# USB_to_UART.net
KiCad netlist of a schematic drawn in Altium Designer
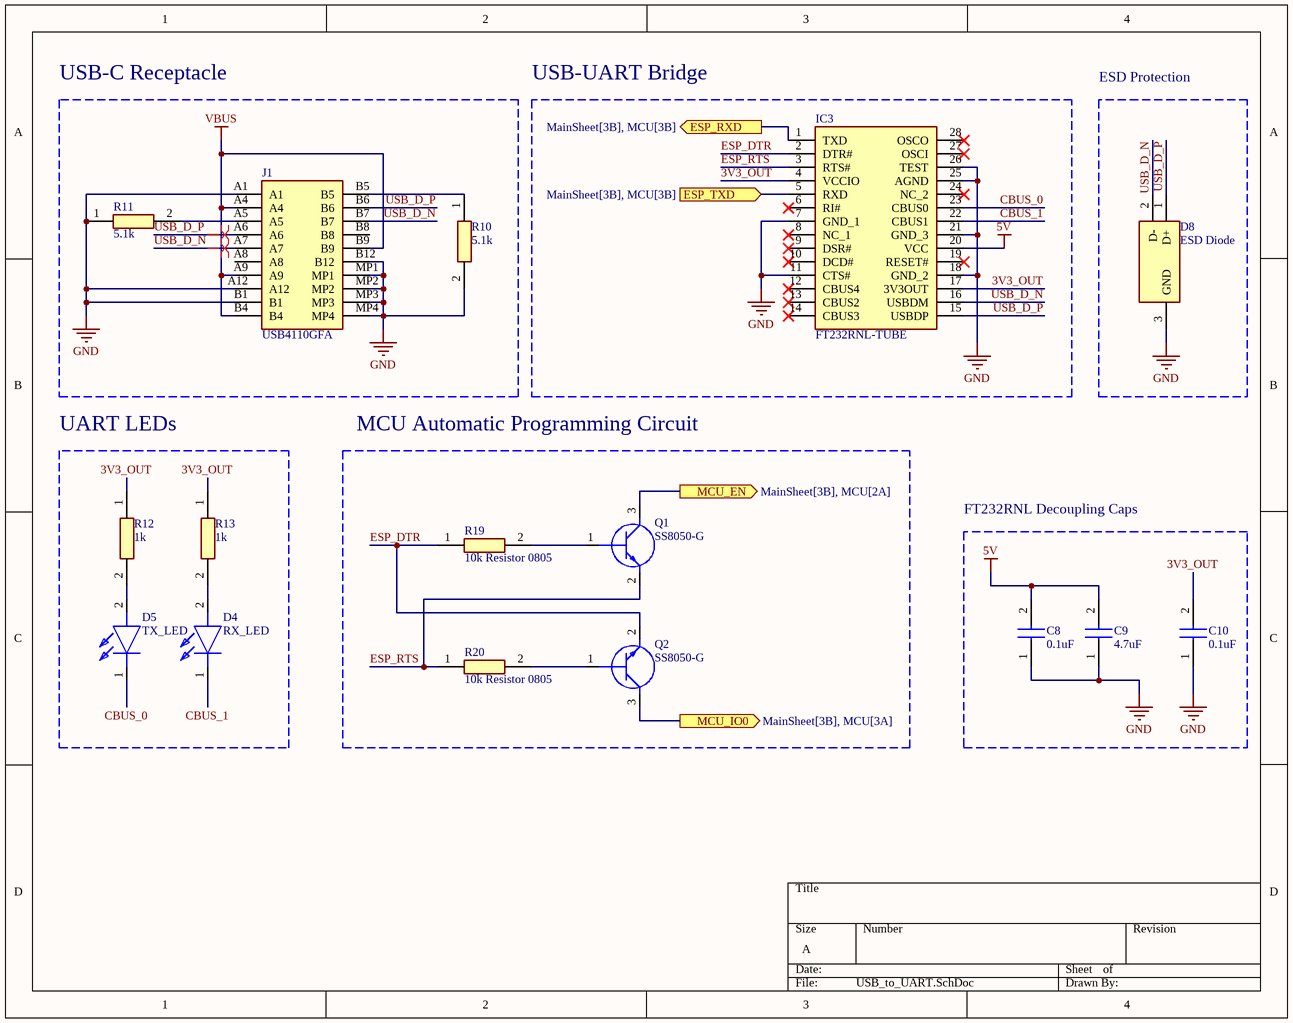
[diagram p0: USB_to_UART.SchDoc]

(export (version "E")
  (design (tool "Eeschema 10.0.6"))
  (components
    (comp (ref "C8")
      (value "0.1uF")
      (footprint "SamacSys:CAPC2012X88N")
      (description "Capacitor")
      (fields (field (name "MANUFACTURER_PART_NUMBER") "C0805C104K5RAC-TU"))
      (libsource (lib "Schlib1") (part "0.1uF Capacitor 0805"))
    )
    (comp (ref "C9")
      (value "4.7uF")
      (footprint "SamacSys:C0805")
      (description "Capacitor")
      (fields
        (field (name "MANUFACTURER_PART_NUMBER") "C0805X475M8RACTU")
        (field (name "MOUSER PART NUMBER") "80-C0805X475M8R")
      )
      (libsource (lib "Schlib1") (part "4.7uF Capacitor 0805"))
    )
    (comp (ref "C10")
      (value "0.1uF")
      (footprint "SamacSys:CAPC2012X88N")
      (description "Capacitor")
      (fields (field (name "MANUFACTURER_PART_NUMBER") "C0805C104K5RAC-TU"))
      (libsource (lib "Schlib1") (part "0.1uF Capacitor 0805"))
    )
    (comp (ref "D4")
      (value "RX_LED")
      (footprint "SamacSys:LEDC2012X85N")
      (description "LED")
      (fields
        (field (name "MANUFACTURER_PART_NUMBER") "APT2012SGC")
        (field (name "MOUSER PART NUMBER") "604-APT2012SGC")
      )
      (libsource (lib "Schlib1") (part "Green LED"))
    )
    (comp (ref "D5")
      (value "TX_LED")
      (footprint "PcbLib1:LEDC2012X85N")
      (description "LED")
      (fields
        (field (name "MANUFACTURER_PART_NUMBER") "APT2012SGC")
        (field (name "MOUSER PART NUMBER") "604-APT2012SGC")
      )
      (libsource (lib "Schlib1") (part "Green LED"))
    )
    (comp (ref "D8")
      (value "ESD Diode")
      (footprint "SamacSys:SOTFL35P100X50-3N")
      (description "Diode")
      (fields
        (field (name "MANUFACTURER_PART_NUMBER") "TPD2EUSB30DRTR")
        (field (name "MOUSER PART NUMBER") "595-TPD2EUSB30DRTR")
      )
      (libsource (lib "Schlib1") (part "ESD Diode"))
    )
    (comp (ref "IC3")
      (value "FT232RNL-TUBE")
      (footprint "SamacSys:SOP65P780X200-28N")
      (description "Integrated Circuit")
      (fields (field (name "MOUSER PART NUMBER") "895-FT232RNL-TUBE"))
      (libsource (lib "Schlib1") (part "FT232RNL-TUBE"))
    )
    (comp (ref "J1")
      (value "USB4110GFA")
      (footprint "SamacSys:USB4110GFA")
      (description "Connector")
      (fields
        (field (name "MANUFACTURER_PART_NUMBER") "USB4110-GF-A")
        (field (name "MOUSER PART NUMBER") "640-USB4110-GF-A")
      )
      (libsource (lib "Schlib1") (part "USB-C Receptacle"))
    )
    (comp (ref "Q1")
      (value "SS8050-G")
      (footprint "SamacSys:SOT95P240X115-3N")
      (description "Transistor BJT NPN")
      (fields (field (name "MOUSER PART NUMBER") "750-SS8050-G"))
      (libsource (lib "Schlib1") (part "SS8050-G"))
    )
    (comp (ref "Q2")
      (value "SS8050-G")
      (footprint "SamacSys:SOT95P240X115-3N")
      (description "Transistor BJT NPN")
      (fields (field (name "MOUSER PART NUMBER") "750-SS8050-G"))
      (libsource (lib "Schlib1") (part "SS8050-G"))
    )
    (comp (ref "R10")
      (value "5.1k")
      (footprint "SamacSys:RESC2012X60N")
      (description "Resistor")
      (fields
        (field (name "MANUFACTURER_PART_NUMBER") "CRCW08055K10JNEAHP")
        (field (name "MOUSER PART NUMBER") "71-CRCW08055K10JNEAH")
      )
      (libsource (lib "Schlib1") (part "5.1k Resistor 0805"))
    )
    (comp (ref "R11")
      (value "5.1k")
      (footprint "SamacSys:RESC2012X60N")
      (description "Resistor")
      (fields
        (field (name "MANUFACTURER_PART_NUMBER") "CRCW08055K10JNEAHP")
        (field (name "MOUSER PART NUMBER") "71-CRCW08055K10JNEAH")
      )
      (libsource (lib "") (part "5.1k Resistor 0805_1"))
    )
    (comp (ref "R12")
      (value "1k")
      (footprint "SamacSys:RESC2012X60N")
      (description "Resistor")
      (fields
        (field (name "MANUFACTURER_PART_NUMBER") "RC0805FR-071KL")
        (field (name "MOUSER PART NUMBER") "603-RC0805FR-071KL")
      )
      (libsource (lib "Schlib1") (part "1k Resistor"))
    )
    (comp (ref "R13")
      (value "1k")
      (footprint "SamacSys:RESC2012X60N")
      (description "Resistor")
      (fields
        (field (name "MANUFACTURER_PART_NUMBER") "RC0805FR-071KL")
        (field (name "MOUSER PART NUMBER") "603-RC0805FR-071KL")
      )
      (libsource (lib "Schlib1") (part "1k Resistor"))
    )
    (comp (ref "R19")
      (value "10k Resistor 0805")
      (footprint "SamacSys:ERA6AEB101V")
      (description "Resistor")
      (fields
        (field (name "MANUFACTURER_PART_NUMBER") "ERA-6AED103V")
        (field (name "MOUSER PART NUMBER") "667-ERA-6AED103V")
      )
      (libsource (lib "Schlib1") (part "10k Resistor 0805"))
    )
    (comp (ref "R20")
      (value "10k Resistor 0805")
      (footprint "SamacSys:ERA6AEB101V")
      (description "Resistor")
      (fields
        (field (name "MANUFACTURER_PART_NUMBER") "ERA-6AED103V")
        (field (name "MOUSER PART NUMBER") "667-ERA-6AED103V")
      )
      (libsource (lib "Schlib1") (part "10k Resistor 0805"))
    )
  )
  (nets
    (net (code "1") (name "/3V3_OUT") (class "Default")
      (node (ref "C10") (pin "2") (pinfunction "2_2") (pintype "passive"))
      (node (ref "IC3") (pin "17") (pinfunction "3V3OUT_17") (pintype "passive"))
      (node (ref "IC3") (pin "4") (pinfunction "VCCIO_4") (pintype "passive"))
      (node (ref "R12") (pin "1") (pinfunction "1_1") (pintype "passive"))
      (node (ref "R13") (pin "1") (pinfunction "1_1") (pintype "passive"))
    )
    (net (code "2") (name "/CBUS_0") (class "Default")
      (node (ref "D5") (pin "1") (pinfunction "K_1") (pintype "passive"))
      (node (ref "IC3") (pin "23") (pinfunction "CBUS0_23") (pintype "passive"))
    )
    (net (code "3") (name "/CBUS_1") (class "Default")
      (node (ref "D4") (pin "1") (pinfunction "K_1") (pintype "passive"))
      (node (ref "IC3") (pin "22") (pinfunction "CBUS1_22") (pintype "passive"))
    )
    (net (code "4") (name "/ESP_DTR") (class "Default")
      (node (ref "IC3") (pin "2") (pinfunction "DTR#_2") (pintype "passive"))
      (node (ref "Q2") (pin "2") (pinfunction "E_2") (pintype "passive"))
      (node (ref "R19") (pin "1") (pinfunction "1_1") (pintype "passive"))
    )
    (net (code "5") (name "/ESP_RTS") (class "Default")
      (node (ref "IC3") (pin "3") (pinfunction "RTS#_3") (pintype "passive"))
      (node (ref "Q1") (pin "2") (pinfunction "E_2") (pintype "passive"))
      (node (ref "R20") (pin "1") (pinfunction "1_1") (pintype "passive"))
    )
    (net (code "6") (name "/ESP_RXD") (class "Default")
      (node (ref "IC3") (pin "1") (pinfunction "TXD_1") (pintype "passive"))
    )
    (net (code "7") (name "/ESP_TXD") (class "Default")
      (node (ref "IC3") (pin "5") (pinfunction "RXD_5") (pintype "passive"))
    )
    (net (code "8") (name "/MCU_EN") (class "Default")
      (node (ref "Q1") (pin "3") (pinfunction "C_3") (pintype "passive"))
    )
    (net (code "9") (name "/MCU_IO0") (class "Default")
      (node (ref "Q2") (pin "3") (pinfunction "C_3") (pintype "passive"))
    )
    (net (code "10") (name "/USB_D_N") (class "Default")
      (node (ref "D8") (pin "2") (pinfunction "D-_2") (pintype "passive"))
      (node (ref "IC3") (pin "16") (pinfunction "USBDM_16") (pintype "passive"))
      (node (ref "J1") (pin "A7") (pinfunction "A7_A7") (pintype "passive"))
      (node (ref "J1") (pin "B7") (pinfunction "B7_B7") (pintype "passive"))
    )
    (net (code "11") (name "/USB_D_P") (class "Default")
      (node (ref "D8") (pin "1") (pinfunction "D+_1") (pintype "passive"))
      (node (ref "IC3") (pin "15") (pinfunction "USBDP_15") (pintype "passive"))
      (node (ref "J1") (pin "A6") (pinfunction "A6_A6") (pintype "passive"))
      (node (ref "J1") (pin "B6") (pinfunction "B6_B6") (pintype "passive"))
    )
    (net (code "12") (name "5V") (class "Default")
      (node (ref "C8") (pin "2") (pinfunction "2_2") (pintype "passive"))
      (node (ref "C9") (pin "2") (pinfunction "2_2") (pintype "passive"))
      (node (ref "IC3") (pin "20") (pinfunction "VCC_20") (pintype "passive"))
    )
    (net (code "13") (name "GND") (class "Default")
      (node (ref "C10") (pin "1") (pinfunction "1_1") (pintype "passive"))
      (node (ref "C8") (pin "1") (pinfunction "1_1") (pintype "passive"))
      (node (ref "C9") (pin "1") (pinfunction "1_1") (pintype "passive"))
      (node (ref "D8") (pin "3") (pinfunction "GND_3") (pintype "passive"))
      (node (ref "IC3") (pin "11") (pinfunction "CTS#_11") (pintype "passive"))
      (node (ref "IC3") (pin "18") (pinfunction "GND_2_18") (pintype "passive"))
      (node (ref "IC3") (pin "21") (pinfunction "GND_3_21") (pintype "passive"))
      (node (ref "IC3") (pin "25") (pinfunction "AGND_25") (pintype "passive"))
      (node (ref "IC3") (pin "26") (pinfunction "TEST_26") (pintype "passive"))
      (node (ref "IC3") (pin "7") (pinfunction "GND_1_7") (pintype "passive"))
      (node (ref "J1") (pin "A1") (pinfunction "A1_A1") (pintype "passive"))
      (node (ref "J1") (pin "A12") (pinfunction "A12_A12") (pintype "passive"))
      (node (ref "J1") (pin "B1") (pinfunction "B1_B1") (pintype "passive"))
      (node (ref "J1") (pin "B12") (pinfunction "B12_B12") (pintype "passive"))
      (node (ref "J1") (pin "MP1") (pinfunction "MP1_MP1") (pintype "passive"))
      (node (ref "J1") (pin "MP2") (pinfunction "MP2_MP2") (pintype "passive"))
      (node (ref "J1") (pin "MP3") (pinfunction "MP3_MP3") (pintype "passive"))
      (node (ref "J1") (pin "MP4") (pinfunction "MP4_MP4") (pintype "passive"))
      (node (ref "R10") (pin "2") (pinfunction "2_2") (pintype "passive"))
      (node (ref "R11") (pin "1") (pinfunction "1_1") (pintype "passive"))
    )
    (net (code "14") (name "Net-(D4-A)") (class "Default")
      (node (ref "D4") (pin "2") (pinfunction "A_2") (pintype "passive"))
      (node (ref "R13") (pin "2") (pinfunction "2_2") (pintype "passive"))
    )
    (net (code "15") (name "Net-(D5-A)") (class "Default")
      (node (ref "D5") (pin "2") (pinfunction "A_2") (pintype "passive"))
      (node (ref "R12") (pin "2") (pinfunction "2_2") (pintype "passive"))
    )
    (net (code "16") (name "Net-(J1-PadA5)") (class "Default")
      (node (ref "J1") (pin "A5") (pinfunction "A5_A5") (pintype "passive"))
      (node (ref "R11") (pin "2") (pinfunction "2_2") (pintype "passive"))
    )
    (net (code "17") (name "Net-(J1-PadB5)") (class "Default")
      (node (ref "J1") (pin "B5") (pinfunction "B5_B5") (pintype "passive"))
      (node (ref "R10") (pin "1") (pinfunction "1_1") (pintype "passive"))
    )
    (net (code "18") (name "Net-(Q1-B)") (class "Default")
      (node (ref "Q1") (pin "1") (pinfunction "B_1") (pintype "passive"))
      (node (ref "R19") (pin "2") (pinfunction "2_2") (pintype "passive"))
    )
    (net (code "19") (name "Net-(Q2-B)") (class "Default")
      (node (ref "Q2") (pin "1") (pinfunction "B_1") (pintype "passive"))
      (node (ref "R20") (pin "2") (pinfunction "2_2") (pintype "passive"))
    )
    (net (code "20") (name "VBUS") (class "Default")
      (node (ref "J1") (pin "A4") (pinfunction "A4_A4") (pintype "passive"))
      (node (ref "J1") (pin "A9") (pinfunction "A9_A9") (pintype "passive"))
      (node (ref "J1") (pin "B4") (pinfunction "B4_B4") (pintype "passive"))
      (node (ref "J1") (pin "B9") (pinfunction "B9_B9") (pintype "passive"))
    )
    (net (code "21") (name "unconnected-(IC3-CBUS2-Pad13)") (class "Default")
      (node (ref "IC3") (pin "13") (pinfunction "CBUS2_13") (pintype "passive+no_connect"))
    )
    (net (code "22") (name "unconnected-(IC3-CBUS3-Pad14)") (class "Default")
      (node (ref "IC3") (pin "14") (pinfunction "CBUS3_14") (pintype "passive+no_connect"))
    )
    (net (code "23") (name "unconnected-(IC3-CBUS4-Pad12)") (class "Default")
      (node (ref "IC3") (pin "12") (pinfunction "CBUS4_12") (pintype "passive+no_connect"))
    )
    (net (code "24") (name "unconnected-(IC3-DCD#-Pad10)") (class "Default")
      (node (ref "IC3") (pin "10") (pinfunction "DCD#_10") (pintype "passive+no_connect"))
    )
    (net (code "25") (name "unconnected-(IC3-DSR#-Pad9)") (class "Default")
      (node (ref "IC3") (pin "9") (pinfunction "DSR#_9") (pintype "passive+no_connect"))
    )
    (net (code "26") (name "unconnected-(IC3-NC_1-Pad8)") (class "Default")
      (node (ref "IC3") (pin "8") (pinfunction "NC_1_8") (pintype "passive+no_connect"))
    )
    (net (code "27") (name "unconnected-(IC3-NC_2-Pad24)") (class "Default")
      (node (ref "IC3") (pin "24") (pinfunction "NC_2_24") (pintype "passive+no_connect"))
    )
    (net (code "28") (name "unconnected-(IC3-OSCI-Pad27)") (class "Default")
      (node (ref "IC3") (pin "27") (pinfunction "OSCI_27") (pintype "passive+no_connect"))
    )
    (net (code "29") (name "unconnected-(IC3-OSCO-Pad28)") (class "Default")
      (node (ref "IC3") (pin "28") (pinfunction "OSCO_28") (pintype "passive+no_connect"))
    )
    (net (code "30") (name "unconnected-(IC3-RESET#-Pad19)") (class "Default")
      (node (ref "IC3") (pin "19") (pinfunction "RESET#_19") (pintype "passive+no_connect"))
    )
    (net (code "31") (name "unconnected-(IC3-RI#-Pad6)") (class "Default")
      (node (ref "IC3") (pin "6") (pinfunction "RI#_6") (pintype "passive+no_connect"))
    )
    (net (code "32") (name "unconnected-(J1-PadA8)") (class "Default")
      (node (ref "J1") (pin "A8") (pinfunction "A8_A8") (pintype "passive"))
    )
    (net (code "33") (name "unconnected-(J1-PadB8)") (class "Default")
      (node (ref "J1") (pin "B8") (pinfunction "B8_B8") (pintype "passive"))
    )
  )
)
